# legacy_mk1_with_acc_16meg_crystal_and_TP.net
KiCad netlist of a schematic drawn in EAGLE
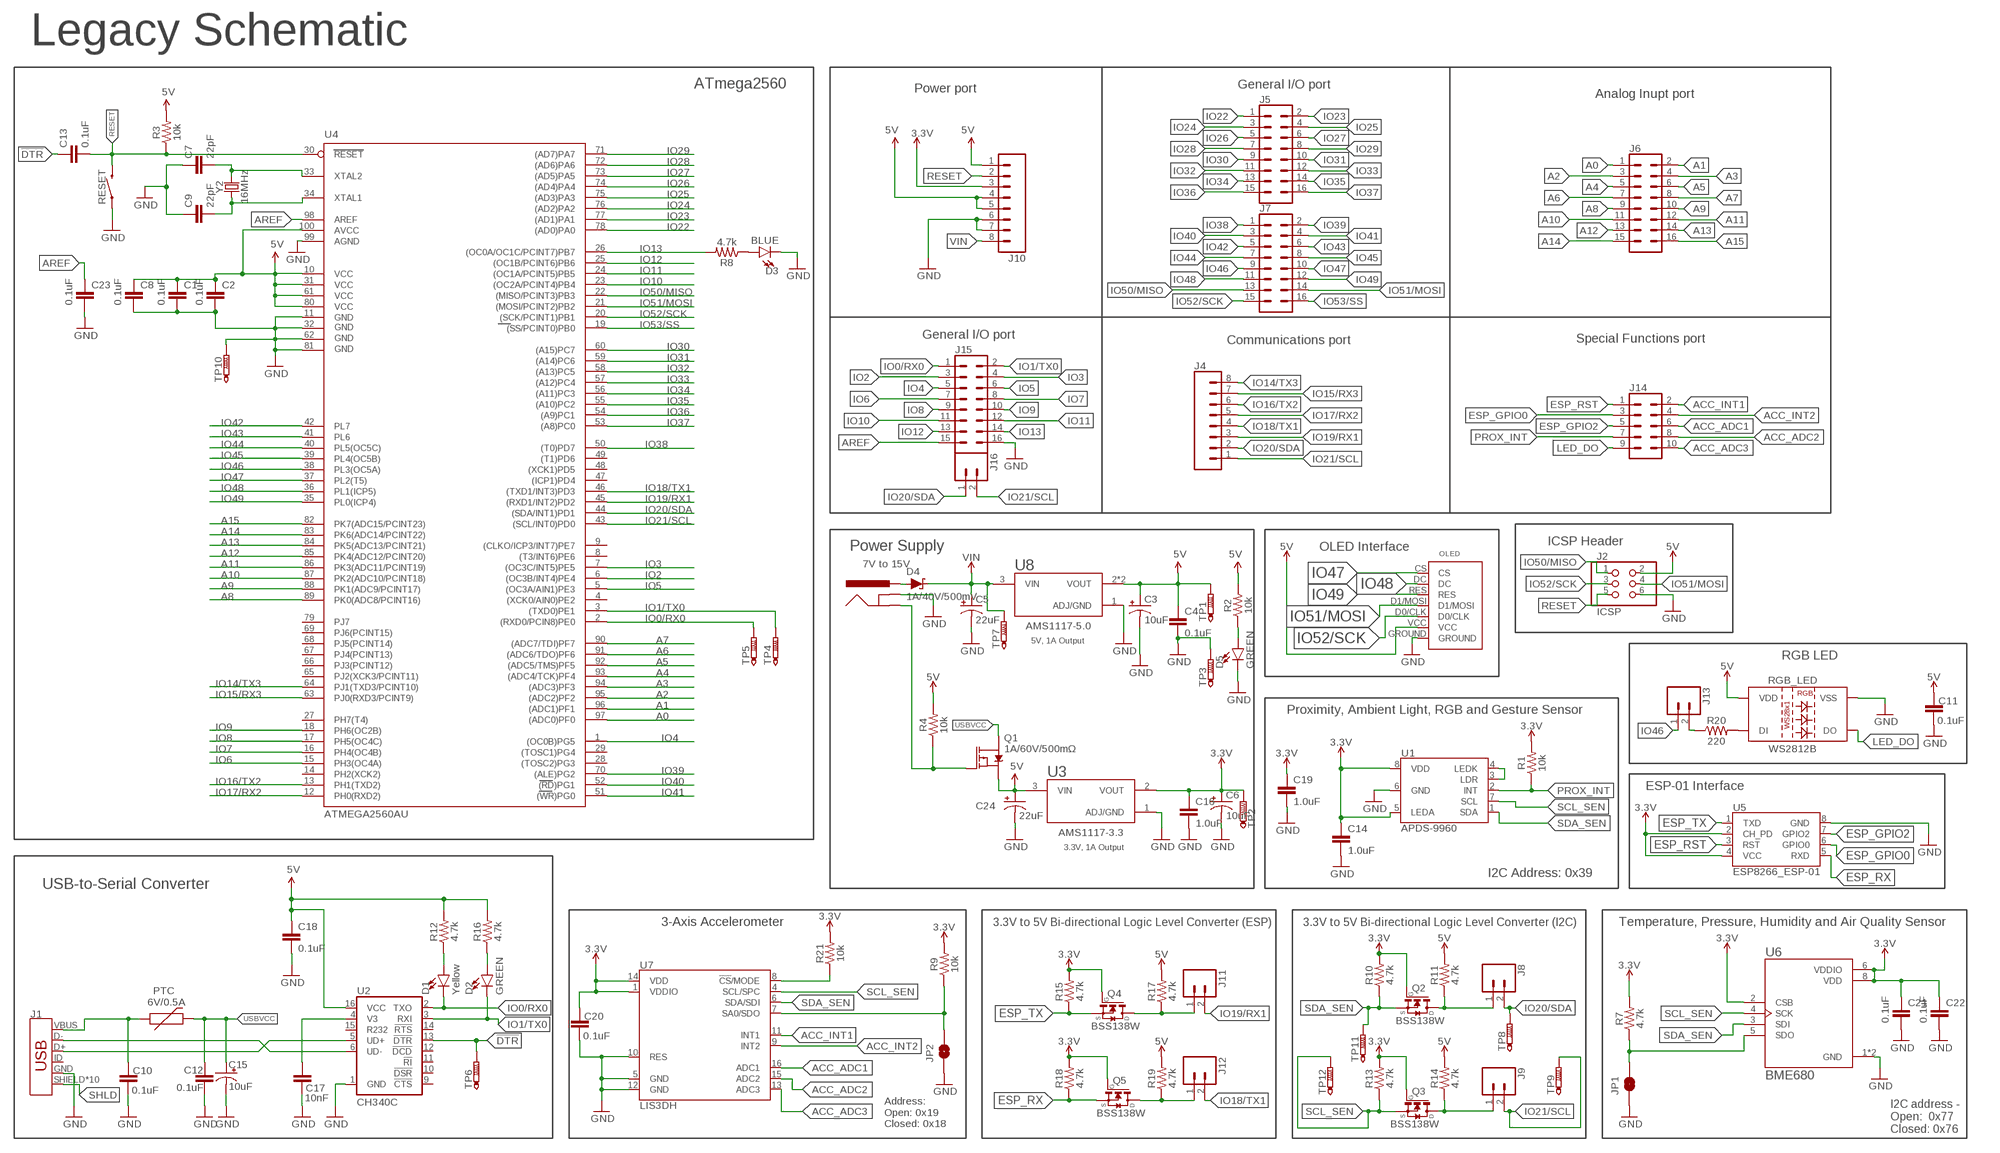
[diagram p0: schematic, sheet 1, part 1 of 2]

(export (version "E")
  (design (tool "Eeschema 10.0.6"))
  (components
    (comp (ref "C1")
      (value "0.1uF")
      (footprint "eagle-import:0603")
      (libsource (lib "eagle-import") (part "0.1UF-0603-25V-(+80/-20%)"))
    )
    (comp (ref "C2")
      (value "0.1uF")
      (footprint "eagle-import:0603")
      (libsource (lib "eagle-import") (part "0.1UF-0603-25V-(+80/-20%)"))
    )
    (comp (ref "C3")
      (value "10uF")
      (footprint "eagle-import:EIA3216")
      (libsource (lib "eagle-import") (part "10UF-POLAR-EIA3216-16V-10%(TANT)"))
    )
    (comp (ref "C4")
      (value "0.1uF")
      (footprint "eagle-import:0603")
      (libsource (lib "eagle-import") (part "0.1UF-0603-25V-(+80/-20%)"))
    )
    (comp (ref "C5")
      (value "22uF")
      (footprint "eagle-import:CT3528")
      (libsource (lib "eagle-import") (part "CPOL-USCT3528"))
    )
    (comp (ref "C6")
      (value "10uF")
      (footprint "eagle-import:EIA3216")
      (libsource (lib "eagle-import") (part "10UF-POLAR-EIA3216-16V-10%(TANT)"))
    )
    (comp (ref "C7")
      (value "22pF")
      (footprint "eagle-import:0603")
      (libsource (lib "eagle-import") (part "22PF-0603-50V-5%"))
    )
    (comp (ref "C8")
      (value "0.1uF")
      (footprint "eagle-import:0603")
      (libsource (lib "eagle-import") (part "0.1UF-0603-25V-(+80/-20%)"))
    )
    (comp (ref "C9")
      (value "22pF")
      (footprint "eagle-import:0603")
      (libsource (lib "eagle-import") (part "22PF-0603-50V-5%"))
    )
    (comp (ref "C10")
      (value "0.1uF")
      (footprint "eagle-import:0603")
      (libsource (lib "eagle-import") (part "0.1UF-0603-25V-(+80/-20%)"))
    )
    (comp (ref "C11")
      (value "0.1uF")
      (footprint "eagle-import:0603")
      (libsource (lib "eagle-import") (part "0.1UF-0603-25V-(+80/-20%)"))
    )
    (comp (ref "C12")
      (value "0.1uF")
      (footprint "eagle-import:0603")
      (libsource (lib "eagle-import") (part "0.1UF-0603-25V-(+80/-20%)"))
    )
    (comp (ref "C13")
      (value "0.1uF")
      (footprint "eagle-import:0603")
      (libsource (lib "eagle-import") (part "0.1UF-0603-25V-(+80/-20%)"))
    )
    (comp (ref "C14")
      (value "1.0uF")
      (footprint "eagle-import:0603-CAP")
      (libsource (lib "eagle-import") (part "1.0UF-16V-10%(0603)"))
    )
    (comp (ref "C15")
      (value "10uF")
      (footprint "eagle-import:EIA3216")
      (libsource (lib "eagle-import") (part "10UF-POLAR-EIA3216-16V-10%(TANT)"))
    )
    (comp (ref "C16")
      (value "1.0uF")
      (footprint "eagle-import:0603-CAP")
      (libsource (lib "eagle-import") (part "1.0UF-16V-10%(0603)"))
    )
    (comp (ref "C17")
      (value "10nF")
      (footprint "eagle-import:0603-CAP")
      (libsource (lib "eagle-import") (part "10NF/10000PF-50V-10%(0603)"))
    )
    (comp (ref "C18")
      (value "0.1uF")
      (footprint "eagle-import:0603")
      (libsource (lib "eagle-import") (part "0.1UF-0603-25V-(+80/-20%)"))
    )
    (comp (ref "C19")
      (value "1.0uF")
      (footprint "eagle-import:0603-CAP")
      (libsource (lib "eagle-import") (part "1.0UF-16V-10%(0603)"))
    )
    (comp (ref "C20")
      (value "0.1uF")
      (footprint "eagle-import:0603")
      (libsource (lib "eagle-import") (part "0.1UF-0603-25V-(+80/-20%)"))
    )
    (comp (ref "C21")
      (value "0.1uF")
      (footprint "eagle-import:0603")
      (libsource (lib "eagle-import") (part "0.1UF-0603-25V-(+80/-20%)"))
    )
    (comp (ref "C22")
      (value "0.1uF")
      (footprint "eagle-import:0603")
      (libsource (lib "eagle-import") (part "0.1UF-0603-25V-(+80/-20%)"))
    )
    (comp (ref "C23")
      (value "0.1uF")
      (footprint "eagle-import:0603")
      (libsource (lib "eagle-import") (part "0.1UF-0603-25V-(+80/-20%)"))
    )
    (comp (ref "C24")
      (value "22uF")
      (footprint "eagle-import:CT3528")
      (libsource (lib "eagle-import") (part "CPOL-USCT3528"))
    )
    (comp (ref "D1")
      (value "Yellow")
      (footprint "eagle-import:LED-0603")
      (libsource (lib "eagle-import") (part "LED-YELLOW0603"))
    )
    (comp (ref "D2")
      (value "GREEN")
      (footprint "eagle-import:LED-0603")
      (libsource (lib "eagle-import") (part "LED-GREEN0603"))
    )
    (comp (ref "D3")
      (value "BLUE")
      (footprint "eagle-import:LED-0603")
      (libsource (lib "eagle-import") (part "LED-BLUE0603"))
    )
    (comp (ref "D4")
      (value "1A/40V/500mV")
      (footprint "eagle-import:SMA-DIODE")
      (libsource (lib "eagle-import") (part "DIODE-SCHOTTKY-SS14"))
    )
    (comp (ref "D5")
      (value "GREEN")
      (footprint "eagle-import:LED-0603")
      (libsource (lib "eagle-import") (part "LED-GREEN0603"))
    )
    (comp (ref "J1")
      (value "AMP FCI 10103594-0001LF")
      (footprint "eagle-import:USB-MICROB-PTH-MILL")
      (libsource (lib "eagle-import") (part "USB_MICRO-B_HALF_PTH_MILL"))
    )
    (comp (ref "J2")
      (value "ICSP")
      (footprint "eagle-import:2X03")
      (libsource (lib "eagle-import") (part "PINHD-2X3"))
    )
    (comp (ref "J3")
      (value "POWER_JACKSLT")
      (footprint "eagle-import:POWER_JACK_SLOT")
      (libsource (lib "eagle-import") (part "POWER_JACKSLT"))
    )
    (comp (ref "J4")
      (value "CONN_08\"")
      (footprint "eagle-import:1X08")
      (libsource (lib "eagle-import") (part "CONN_08{dblquote}"))
    )
    (comp (ref "J5")
      (value "CONN_08X2_HEADER")
      (footprint "eagle-import:2X8")
      (libsource (lib "eagle-import") (part "CONN_08X2_HEADER"))
    )
    (comp (ref "J6")
      (value "CONN_08X2_HEADER")
      (footprint "eagle-import:2X8")
      (libsource (lib "eagle-import") (part "CONN_08X2_HEADER"))
    )
    (comp (ref "J7")
      (value "CONN_08X2_HEADER")
      (footprint "eagle-import:2X8")
      (libsource (lib "eagle-import") (part "CONN_08X2_HEADER"))
    )
    (comp (ref "J8")
      (value "CONN_02")
      (footprint "eagle-import:1X02")
      (libsource (lib "eagle-import") (part "CONN_02"))
    )
    (comp (ref "J9")
      (value "CONN_02")
      (footprint "eagle-import:1X02")
      (libsource (lib "eagle-import") (part "CONN_02"))
    )
    (comp (ref "J10")
      (value "CONN_08\"")
      (footprint "eagle-import:1X08")
      (libsource (lib "eagle-import") (part "CONN_08{dblquote}"))
    )
    (comp (ref "J11")
      (value "CONN_02")
      (footprint "eagle-import:1X02")
      (libsource (lib "eagle-import") (part "CONN_02"))
    )
    (comp (ref "J12")
      (value "CONN_02")
      (footprint "eagle-import:1X02")
      (libsource (lib "eagle-import") (part "CONN_02"))
    )
    (comp (ref "J13")
      (value "CONN_02")
      (footprint "eagle-import:1X02")
      (libsource (lib "eagle-import") (part "CONN_02"))
    )
    (comp (ref "J14")
      (value "CONN_05X2PTH")
      (footprint "eagle-import:2X5")
      (libsource (lib "eagle-import") (part "CONN_05X2PTH"))
    )
    (comp (ref "J15")
      (value "CONN_08X2_HEADER")
      (footprint "eagle-import:2X8")
      (libsource (lib "eagle-import") (part "CONN_08X2_HEADER"))
    )
    (comp (ref "J16")
      (value "CONN_02")
      (footprint "eagle-import:1X02")
      (libsource (lib "eagle-import") (part "CONN_02"))
    )
    (comp (ref "JP1")
      (value "JUMPER-SMT_2_NO_SILK")
      (footprint "eagle-import:SMT-JUMPER_2_NO_SILK")
      (libsource (lib "eagle-import") (part "JUMPER-SMT_2_NO_SILK"))
    )
    (comp (ref "JP2")
      (value "JUMPER-SMT_2_NO_SILK")
      (footprint "eagle-import:SMT-JUMPER_2_NO_SILK")
      (libsource (lib "eagle-import") (part "JUMPER-SMT_2_NO_SILK"))
    )
    (comp (ref "OLED")
      (value "OLED_SHIELD")
      (footprint "eagle-import:OLED_SHIELD")
      (libsource (lib "eagle-import") (part "OLED_SHIELD"))
    )
    (comp (ref "PTC")
      (value "6V/0.5A")
      (footprint "eagle-import:1206")
      (libsource (lib "eagle-import") (part "PPTC_6V500MA-2"))
    )
    (comp (ref "Q1")
      (value "1A/60V/500mΩ")
      (footprint "eagle-import:SOT23-3")
      (libsource (lib "eagle-import") (part "MOSFET-PCH-ZXMP6A13F"))
    )
    (comp (ref "Q2")
      (value "BSS138W")
      (footprint "eagle-import:SOT323-R")
      (fields (field (name "DIGI-KEY_PART_NUMBER") "BSS138WCT-ND") (field (name "MF") "ON Semiconductor"))
      (libsource (lib "eagle-import") (part "BSS138W"))
    )
    (comp (ref "Q3")
      (value "BSS138W")
      (footprint "eagle-import:SOT323-R")
      (fields (field (name "DIGI-KEY_PART_NUMBER") "BSS138WCT-ND") (field (name "MF") "ON Semiconductor"))
      (libsource (lib "eagle-import") (part "BSS138W"))
    )
    (comp (ref "Q4")
      (value "BSS138W")
      (footprint "eagle-import:SOT323-R")
      (fields (field (name "DIGI-KEY_PART_NUMBER") "BSS138WCT-ND") (field (name "MF") "ON Semiconductor"))
      (libsource (lib "eagle-import") (part "BSS138W"))
    )
    (comp (ref "Q5")
      (value "BSS138W")
      (footprint "eagle-import:SOT323-R")
      (fields (field (name "DIGI-KEY_PART_NUMBER") "BSS138WCT-ND") (field (name "MF") "ON Semiconductor"))
      (libsource (lib "eagle-import") (part "BSS138W"))
    )
    (comp (ref "R1")
      (value "10k")
      (footprint "eagle-import:0603")
      (libsource (lib "eagle-import") (part "10KOHM-0603-1/10W-1%"))
    )
    (comp (ref "R2")
      (value "10k")
      (footprint "eagle-import:0603")
      (libsource (lib "eagle-import") (part "10KOHM-0603-1/10W-1%"))
    )
    (comp (ref "R3")
      (value "10k")
      (footprint "eagle-import:0603")
      (libsource (lib "eagle-import") (part "10KOHM-0603-1/10W-1%"))
    )
    (comp (ref "R4")
      (value "10k")
      (footprint "eagle-import:0603")
      (libsource (lib "eagle-import") (part "10KOHM-0603-1/10W-1%"))
    )
    (comp (ref "R7")
      (value "4.7k")
      (footprint "eagle-import:0603")
      (libsource (lib "eagle-import") (part "4.7KOHM-0603-1/10W-1%"))
    )
    (comp (ref "R8")
      (value "4.7k")
      (footprint "eagle-import:0603")
      (libsource (lib "eagle-import") (part "4.7KOHM-0603-1/10W-1%"))
    )
    (comp (ref "R9")
      (value "10k")
      (footprint "eagle-import:0603")
      (libsource (lib "eagle-import") (part "10KOHM-0603-1/10W-1%"))
    )
    (comp (ref "R10")
      (value "4.7k")
      (footprint "eagle-import:0603")
      (libsource (lib "eagle-import") (part "4.7KOHM-0603-1/10W-1%"))
    )
    (comp (ref "R11")
      (value "4.7k")
      (footprint "eagle-import:0603")
      (libsource (lib "eagle-import") (part "4.7KOHM-0603-1/10W-1%"))
    )
    (comp (ref "R12")
      (value "4.7k")
      (footprint "eagle-import:0603")
      (libsource (lib "eagle-import") (part "4.7KOHM-0603-1/10W-1%"))
    )
    (comp (ref "R13")
      (value "4.7k")
      (footprint "eagle-import:0603")
      (libsource (lib "eagle-import") (part "4.7KOHM-0603-1/10W-1%"))
    )
    (comp (ref "R14")
      (value "4.7k")
      (footprint "eagle-import:0603")
      (libsource (lib "eagle-import") (part "4.7KOHM-0603-1/10W-1%"))
    )
    (comp (ref "R15")
      (value "4.7k")
      (footprint "eagle-import:0603")
      (libsource (lib "eagle-import") (part "4.7KOHM-0603-1/10W-1%"))
    )
    (comp (ref "R16")
      (value "4.7k")
      (footprint "eagle-import:0603")
      (libsource (lib "eagle-import") (part "4.7KOHM-0603-1/10W-1%"))
    )
    (comp (ref "R17")
      (value "4.7k")
      (footprint "eagle-import:0603")
      (libsource (lib "eagle-import") (part "4.7KOHM-0603-1/10W-1%"))
    )
    (comp (ref "R18")
      (value "4.7k")
      (footprint "eagle-import:0603")
      (libsource (lib "eagle-import") (part "4.7KOHM-0603-1/10W-1%"))
    )
    (comp (ref "R19")
      (value "4.7k")
      (footprint "eagle-import:0603")
      (libsource (lib "eagle-import") (part "4.7KOHM-0603-1/10W-1%"))
    )
    (comp (ref "R20")
      (value "220")
      (footprint "eagle-import:0603")
      (libsource (lib "eagle-import") (part "220OHM-0603-1/10W-1%"))
    )
    (comp (ref "R21")
      (value "10k")
      (footprint "eagle-import:0603")
      (libsource (lib "eagle-import") (part "10KOHM-0603-1/10W-1%"))
    )
    (comp (ref "RESET")
      (value "MOMENTARY-SWITCH-SPST-PTH-6.0MM")
      (footprint "eagle-import:TACTILE_SWITCH_PTH_6.0MM")
      (libsource (lib "eagle-import") (part "MOMENTARY-SWITCH-SPST-PTH-6.0MM"))
    )
    (comp (ref "RGB_LED")
      (value "WS2812B")
      (footprint "eagle-import:WS2812B")
      (libsource (lib "eagle-import") (part "WS2812B"))
    )
    (comp (ref "TP1")
      (value "PTR1B1,27")
      (footprint "eagle-import:B1,27")
      (libsource (lib "eagle-import") (part "PTR1B1,27"))
    )
    (comp (ref "TP2")
      (value "PTR1B1,27")
      (footprint "eagle-import:B1,27")
      (libsource (lib "eagle-import") (part "PTR1B1,27"))
    )
    (comp (ref "TP3")
      (value "PTR1B1,27")
      (footprint "eagle-import:B1,27")
      (libsource (lib "eagle-import") (part "PTR1B1,27"))
    )
    (comp (ref "TP4")
      (value "PTR1B1,27")
      (footprint "eagle-import:B1,27")
      (libsource (lib "eagle-import") (part "PTR1B1,27"))
    )
    (comp (ref "TP5")
      (value "PTR1B1,27")
      (footprint "eagle-import:B1,27")
      (libsource (lib "eagle-import") (part "PTR1B1,27"))
    )
    (comp (ref "TP6")
      (value "PTR1B1,27")
      (footprint "eagle-import:B1,27")
      (libsource (lib "eagle-import") (part "PTR1B1,27"))
    )
    (comp (ref "TP7")
      (value "PTR1B1,27")
      (footprint "eagle-import:B1,27")
      (libsource (lib "eagle-import") (part "PTR1B1,27"))
    )
    (comp (ref "TP8")
      (value "PTR1B1,27")
      (footprint "eagle-import:B1,27")
      (libsource (lib "eagle-import") (part "PTR1B1,27"))
    )
    (comp (ref "TP9")
      (value "PTR1B1,27")
      (footprint "eagle-import:B1,27")
      (libsource (lib "eagle-import") (part "PTR1B1,27"))
    )
    (comp (ref "TP10")
      (value "PTR1B1,27")
      (footprint "eagle-import:B1,27")
      (libsource (lib "eagle-import") (part "PTR1B1,27"))
    )
    (comp (ref "TP11")
      (value "PTR1B1,27")
      (footprint "eagle-import:B1,27")
      (libsource (lib "eagle-import") (part "PTR1B1,27"))
    )
    (comp (ref "TP12")
      (value "PTR1B1,27")
      (footprint "eagle-import:B1,27")
      (libsource (lib "eagle-import") (part "PTR1B1,27"))
    )
    (comp (ref "U1")
      (value "APDS-9960")
      (footprint "eagle-import:APDS-9960")
      (fields (field (name "MF") "Broadcom Limited"))
      (libsource (lib "eagle-import") (part "APDS-9960"))
    )
    (comp (ref "U2")
      (value "CH340C")
      (footprint "eagle-import:SO016")
      (libsource (lib "eagle-import") (part "CH340C"))
    )
    (comp (ref "U3")
      (value "AMS1117-3.3")
      (footprint "eagle-import:SOT229P700X180-4N")
      (fields (field (name "MF") "Advanced Monolithic Systems"))
      (libsource (lib "eagle-import") (part "AMS1117-3.3"))
    )
    (comp (ref "U4")
      (value "ATMEGA2560AU")
      (footprint "eagle-import:TQFP100")
      (libsource (lib "eagle-import") (part "ATMEGA2560AU"))
    )
    (comp (ref "U5")
      (value "ESP8266_ESP-01")
      (footprint "eagle-import:ESP8266_ESP-01")
      (libsource (lib "eagle-import") (part "ESP8266_ESP-01"))
    )
    (comp (ref "U6")
      (value "BME680")
      (footprint "eagle-import:PSON80P300X300X100-8N")
      (fields (field (name "DIGI-KEY_PART_NUMBER") "828-1077-1-ND") (field (name "MF") "Bosch Sensortec"))
      (libsource (lib "eagle-import") (part "BME680"))
    )
    (comp (ref "U7")
      (value "LIS3DH")
      (footprint "eagle-import:LGA-16-3X3")
      (libsource (lib "eagle-import") (part "LIS3DH"))
    )
    (comp (ref "U8")
      (value "AMS1117-5.0")
      (footprint "eagle-import:SOT229P700X180-4N")
      (fields (field (name "MF") "Advanced Monolithic Systems"))
      (libsource (lib "eagle-import") (part "AMS1117-5.0"))
    )
    (comp (ref "Y2")
      (value "16MHz")
      (footprint "eagle-import:HC49US")
      (libsource (lib "eagle-import") (part "CRYSTAL-16MHZPTH-HC49US"))
    )
  )
  (nets
    (net (code "1") (name "/~{DTR}") (class "Default")
      (node (ref "C13") (pin "1") (pinfunction "1_1") (pintype "passive"))
      (node (ref "TP6") (pin "TP") (pinfunction "TP_TP") (pintype "input"))
      (node (ref "U2") (pin "13") (pinfunction "~{DTR}_13") (pintype "bidirectional"))
    )
    (net (code "2") (name "3.3V") (class "Default")
      (node (ref "C14") (pin "1") (pinfunction "1_1") (pintype "passive"))
      (node (ref "C16") (pin "1") (pinfunction "1_1") (pintype "passive"))
      (node (ref "C19") (pin "1") (pinfunction "1_1") (pintype "passive"))
      (node (ref "C20") (pin "1") (pinfunction "1_1") (pintype "passive"))
      (node (ref "C21") (pin "1") (pinfunction "1_1") (pintype "passive"))
      (node (ref "C22") (pin "1") (pinfunction "1_1") (pintype "passive"))
      (node (ref "C6") (pin "+") (pinfunction "+_+") (pintype "passive"))
      (node (ref "J10") (pin "3") (pinfunction "3_3") (pintype "passive"))
      (node (ref "Q2") (pin "1") (pinfunction "G_1") (pintype "passive"))
      (node (ref "Q3") (pin "1") (pinfunction "G_1") (pintype "passive"))
      (node (ref "Q4") (pin "1") (pinfunction "G_1") (pintype "passive"))
      (node (ref "Q5") (pin "1") (pinfunction "G_1") (pintype "passive"))
      (node (ref "R1") (pin "2") (pinfunction "2_2") (pintype "passive"))
      (node (ref "R10") (pin "2") (pinfunction "2_2") (pintype "passive"))
      (node (ref "R13") (pin "2") (pinfunction "2_2") (pintype "passive"))
      (node (ref "R15") (pin "2") (pinfunction "2_2") (pintype "passive"))
      (node (ref "R18") (pin "2") (pinfunction "2_2") (pintype "passive"))
      (node (ref "R21") (pin "2") (pinfunction "2_2") (pintype "passive"))
      (node (ref "R7") (pin "2") (pinfunction "2_2") (pintype "passive"))
      (node (ref "R9") (pin "2") (pinfunction "2_2") (pintype "passive"))
      (node (ref "TP2") (pin "TP") (pinfunction "TP_TP") (pintype "input"))
      (node (ref "U1") (pin "5") (pinfunction "LEDA_5") (pintype "bidirectional"))
      (node (ref "U1") (pin "8") (pinfunction "VDD_8") (pintype "bidirectional"))
      (node (ref "U3") (pin "2") (pinfunction "VOUT_2") (pintype "output"))
      (node (ref "U5") (pin "2") (pinfunction "CH_PD_2") (pintype "bidirectional"))
      (node (ref "U5") (pin "4") (pinfunction "VCC_4") (pintype "bidirectional"))
      (node (ref "U6") (pin "2") (pinfunction "CSB_2") (pintype "input"))
      (node (ref "U6") (pin "6") (pinfunction "VDDIO_6") (pintype "power_in"))
      (node (ref "U6") (pin "8") (pinfunction "VDD_8") (pintype "power_in"))
      (node (ref "U7") (pin "1") (pinfunction "VDDIO_1") (pintype "bidirectional"))
      (node (ref "U7") (pin "14") (pinfunction "VDD_14") (pintype "bidirectional"))
    )
    (net (code "3") (name "5V") (class "Default")
      (node (ref "C1") (pin "1") (pinfunction "1_1") (pintype "passive"))
      (node (ref "C11") (pin "1") (pinfunction "1_1") (pintype "passive"))
      (node (ref "C18") (pin "1") (pinfunction "1_1") (pintype "passive"))
      (node (ref "C2") (pin "1") (pinfunction "1_1") (pintype "passive"))
      (node (ref "C24") (pin "+") (pinfunction "+_+") (pintype "passive"))
      (node (ref "C3") (pin "+") (pinfunction "+_+") (pintype "passive"))
      (node (ref "C4") (pin "1") (pinfunction "1_1") (pintype "passive"))
      (node (ref "C8") (pin "1") (pinfunction "1_1") (pintype "passive"))
      (node (ref "J10") (pin "1") (pinfunction "1_1") (pintype "passive"))
      (node (ref "J10") (pin "4") (pinfunction "4_4") (pintype "passive"))
      (node (ref "J10") (pin "5") (pinfunction "5_5") (pintype "passive"))
      (node (ref "J2") (pin "2") (pinfunction "2_2") (pintype "passive"))
      (node (ref "OLED") (pin "VCC") (pinfunction "VCC_VCC") (pintype "bidirectional"))
      (node (ref "Q1") (pin "2") (pinfunction "S_2") (pintype "bidirectional"))
      (node (ref "R11") (pin "2") (pinfunction "2_2") (pintype "passive"))
      (node (ref "R12") (pin "2") (pinfunction "2_2") (pintype "passive"))
      (node (ref "R14") (pin "2") (pinfunction "2_2") (pintype "passive"))
      (node (ref "R16") (pin "2") (pinfunction "2_2") (pintype "passive"))
      (node (ref "R17") (pin "2") (pinfunction "2_2") (pintype "passive"))
      (node (ref "R19") (pin "2") (pinfunction "2_2") (pintype "passive"))
      (node (ref "R2") (pin "2") (pinfunction "2_2") (pintype "passive"))
      (node (ref "R3") (pin "2") (pinfunction "2_2") (pintype "passive"))
      (node (ref "R4") (pin "2") (pinfunction "2_2") (pintype "passive"))
      (node (ref "RGB_LED") (pin "1") (pinfunction "VDD_1") (pintype "bidirectional"))
      (node (ref "TP1") (pin "TP") (pinfunction "TP_TP") (pintype "input"))
      (node (ref "U2") (pin "16") (pinfunction "VCC_16") (pintype "bidirectional"))
      (node (ref "U3") (pin "3") (pinfunction "VIN_3") (pintype "input"))
      (node (ref "U4") (pin "10") (pinfunction "VCC_10") (pintype "power_in"))
      (node (ref "U4") (pin "100") (pinfunction "AVCC_100") (pintype "power_in"))
      (node (ref "U4") (pin "31") (pinfunction "VCC1_31") (pintype "power_in"))
      (node (ref "U4") (pin "61") (pinfunction "VCC2_61") (pintype "power_in"))
      (node (ref "U4") (pin "80") (pinfunction "VCC3_80") (pintype "power_in"))
      (node (ref "U8") (pin "2") (pinfunction "VOUT_2") (pintype "output"))
      (node (ref "U8") (pin "4") (pinfunction "VOUT_4") (pintype "output"))
    )
    (net (code "4") (name "A0") (class "Default")
      (node (ref "J6") (pin "1") (pinfunction "1_1") (pintype "passive"))
      (node (ref "U4") (pin "97") (pinfunction "(ADC0)PF0_97") (pintype "bidirectional"))
    )
    (net (code "5") (name "A1") (class "Default")
      (node (ref "J6") (pin "2") (pinfunction "2_2") (pintype "passive"))
      (node (ref "U4") (pin "96") (pinfunction "(ADC1)PF1_96") (pintype "bidirectional"))
    )
    (net (code "6") (name "A2") (class "Default")
      (node (ref "J6") (pin "3") (pinfunction "3_3") (pintype "passive"))
      (node (ref "U4") (pin "95") (pinfunction "(ADC2)PF2_95") (pintype "bidirectional"))
    )
    (net (code "7") (name "A3") (class "Default")
      (node (ref "J6") (pin "4") (pinfunction "4_4") (pintype "passive"))
      (node (ref "U4") (pin "94") (pinfunction "(ADC3)PF3_94") (pintype "bidirectional"))
    )
    (net (code "8") (name "A4") (class "Default")
      (node (ref "J6") (pin "5") (pinfunction "5_5") (pintype "passive"))
      (node (ref "U4") (pin "93") (pinfunction "(ADC4/TCK)PF4_93") (pintype "bidirectional"))
    )
    (net (code "9") (name "A5") (class "Default")
      (node (ref "J6") (pin "6") (pinfunction "6_6") (pintype "passive"))
      (node (ref "U4") (pin "92") (pinfunction "(ADC5/TMS)PF5_92") (pintype "bidirectional"))
    )
    (net (code "10") (name "A6") (class "Default")
      (node (ref "J6") (pin "7") (pinfunction "7_7") (pintype "passive"))
      (node (ref "U4") (pin "91") (pinfunction "(ADC6/TDO)PF6_91") (pintype "bidirectional"))
    )
    (net (code "11") (name "A7") (class "Default")
      (node (ref "J6") (pin "8") (pinfunction "8_8") (pintype "passive"))
      (node (ref "U4") (pin "90") (pinfunction "(ADC7/TDI)PF7_90") (pintype "bidirectional"))
    )
    (net (code "12") (name "A8") (class "Default")
      (node (ref "J6") (pin "9") (pinfunction "9_9") (pintype "passive"))
      (node (ref "U4") (pin "89") (pinfunction "PK0(ADC8/PCINT16)_89") (pintype "bidirectional"))
    )
    (net (code "13") (name "A9") (class "Default")
      (node (ref "J6") (pin "10") (pinfunction "10_10") (pintype "passive"))
      (node (ref "U4") (pin "88") (pinfunction "PK1(ADC9/PCINT17)_88") (pintype "bidirectional"))
    )
    (net (code "14") (name "A10") (class "Default")
      (node (ref "J6") (pin "11") (pinfunction "11_11") (pintype "passive"))
      (node (ref "U4") (pin "87") (pinfunction "PK2(ADC10/PCINT18)_87") (pintype "bidirectional"))
    )
    (net (code "15") (name "A11") (class "Default")
      (node (ref "J6") (pin "12") (pinfunction "12_12") (pintype "passive"))
      (node (ref "U4") (pin "86") (pinfunction "PK3(ADC11/PCINT19)_86") (pintype "bidirectional"))
    )
    (net (code "16") (name "A12") (class "Default")
      (node (ref "J6") (pin "13") (pinfunction "13_13") (pintype "passive"))
      (node (ref "U4") (pin "85") (pinfunction "PK4(ADC12/PCINT20)_85") (pintype "bidirectional"))
    )
    (net (code "17") (name "A13") (class "Default")
      (node (ref "J6") (pin "14") (pinfunction "14_14") (pintype "passive"))
      (node (ref "U4") (pin "84") (pinfunction "PK5(ADC13/PCINT21)_84") (pintype "bidirectional"))
    )
    (net (code "18") (name "A14") (class "Default")
      (node (ref "J6") (pin "15") (pinfunction "15_15") (pintype "passive"))
      (node (ref "U4") (pin "83") (pinfunction "PK6(ADC14/PCINT22)_83") (pintype "bidirectional"))
    )
    (net (code "19") (name "A15") (class "Default")
      (node (ref "J6") (pin "16") (pinfunction "16_16") (pintype "passive"))
      (node (ref "U4") (pin "82") (pinfunction "PK7(ADC15/PCINT23)_82") (pintype "bidirectional"))
    )
    (net (code "20") (name "ACC_ADC1") (class "Default")
      (node (ref "J14") (pin "6") (pinfunction "6_6") (pintype "passive"))
      (node (ref "U7") (pin "16") (pinfunction "ADC1_16") (pintype "bidirectional"))
    )
    (net (code "21") (name "ACC_ADC2") (class "Default")
      (node (ref "J14") (pin "8") (pinfunction "8_8") (pintype "passive"))
      (node (ref "U7") (pin "15") (pinfunction "ADC2_15") (pintype "bidirectional"))
    )
    (net (code "22") (name "ACC_ADC3") (class "Default")
      (node (ref "J14") (pin "10") (pinfunction "10_10") (pintype "passive"))
      (node (ref "U7") (pin "13") (pinfunction "ADC3_13") (pintype "bidirectional"))
    )
    (net (code "23") (name "ACC_INT1") (class "Default")
      (node (ref "J14") (pin "2") (pinfunction "2_2") (pintype "passive"))
      (node (ref "U7") (pin "11") (pinfunction "INT1_11") (pintype "bidirectional"))
    )
    (net (code "24") (name "ACC_INT2") (class "Default")
      (node (ref "J14") (pin "4") (pinfunction "4_4") (pintype "passive"))
      (node (ref "U7") (pin "9") (pinfunction "INT2_9") (pintype "bidirectional"))
    )
    (net (code "25") (name "AREF") (class "Default")
      (node (ref "C23") (pin "1") (pinfunction "1_1") (pintype "passive"))
      (node (ref "J15") (pin "15") (pinfunction "15_15") (pintype "passive"))
      (node (ref "U4") (pin "98") (pinfunction "AREF_98") (pintype "bidirectional"))
    )
    (net (code "26") (name "ESP_GPIO0") (class "Default")
      (node (ref "J14") (pin "3") (pinfunction "3_3") (pintype "passive"))
      (node (ref "U5") (pin "6") (pinfunction "GPIO0_6") (pintype "bidirectional"))
    )
    (net (code "27") (name "ESP_GPIO2") (class "Default")
      (node (ref "J14") (pin "5") (pinfunction "5_5") (pintype "passive"))
      (node (ref "U5") (pin "7") (pinfunction "GPIO2_7") (pintype "bidirectional"))
    )
    (net (code "28") (name "ESP_RST") (class "Default")
      (node (ref "J14") (pin "1") (pinfunction "1_1") (pintype "passive"))
      (node (ref "U5") (pin "3") (pinfunction "RST_3") (pintype "bidirectional"))
    )
    (net (code "29") (name "ESP_RX") (class "Default")
      (node (ref "Q5") (pin "2") (pinfunction "S_2") (pintype "passive"))
      (node (ref "R18") (pin "1") (pinfunction "1_1") (pintype "passive"))
      (node (ref "U5") (pin "5") (pinfunction "RXD_5") (pintype "bidirectional"))
    )
    (net (code "30") (name "ESP_TX") (class "Default")
      (node (ref "Q4") (pin "2") (pinfunction "S_2") (pintype "passive"))
      (node (ref "R15") (pin "1") (pinfunction "1_1") (pintype "passive"))
      (node (ref "U5") (pin "1") (pinfunction "TXD_1") (pintype "bidirectional"))
    )
    (net (code "31") (name "GND") (class "Default")
      (node (ref "C1") (pin "2") (pinfunction "2_2") (pintype "passive"))
      (node (ref "C10") (pin "2") (pinfunction "2_2") (pintype "passive"))
      (node (ref "C11") (pin "2") (pinfunction "2_2") (pintype "passive"))
      (node (ref "C12") (pin "2") (pinfunction "2_2") (pintype "passive"))
      (node (ref "C14") (pin "2") (pinfunction "2_2") (pintype "passive"))
      (node (ref "C15") (pin "-") (pinfunction "-_-") (pintype "passive"))
      (node (ref "C16") (pin "2") (pinfunction "2_2") (pintype "passive"))
      (node (ref "C17") (pin "2") (pinfunction "2_2") (pintype "passive"))
      (node (ref "C18") (pin "2") (pinfunction "2_2") (pintype "passive"))
      (node (ref "C19") (pin "2") (pinfunction "2_2") (pintype "passive"))
      (node (ref "C2") (pin "2") (pinfunction "2_2") (pintype "passive"))
      (node (ref "C20") (pin "2") (pinfunction "2_2") (pintype "passive"))
      (node (ref "C21") (pin "2") (pinfunction "2_2") (pintype "passive"))
      (node (ref "C22") (pin "2") (pinfunction "2_2") (pintype "passive"))
      (node (ref "C23") (pin "2") (pinfunction "2_2") (pintype "passive"))
      (node (ref "C24") (pin "-") (pinfunction "-_-") (pintype "passive"))
      (node (ref "C3") (pin "-") (pinfunction "-_-") (pintype "passive"))
      (node (ref "C4") (pin "2") (pinfunction "2_2") (pintype "passive"))
      (node (ref "C5") (pin "-") (pinfunction "-_-") (pintype "passive"))
      (node (ref "C6") (pin "-") (pinfunction "-_-") (pintype "passive"))
      (node (ref "C7") (pin "1") (pinfunction "1_1") (pintype "passive"))
      (node (ref "C8") (pin "2") (pinfunction "2_2") (pintype "passive"))
      (node (ref "C9") (pin "1") (pinfunction "1_1") (pintype "passive"))
      (node (ref "D3") (pin "C") (pinfunction "C_C") (pintype "passive"))
      (node (ref "D5") (pin "C") (pinfunction "C_C") (pintype "passive"))
      (node (ref "J1") (pin "GND") (pinfunction "GND_GND") (pintype "power_in"))
      (node (ref "J10") (pin "6") (pinfunction "6_6") (pintype "passive"))
      (node (ref "J10") (pin "7") (pinfunction "7_7") (pintype "passive"))
      (node (ref "J15") (pin "16") (pinfunction "16_16") (pintype "passive"))
      (node (ref "J2") (pin "6") (pinfunction "6_6") (pintype "passive"))
      (node (ref "J3") (pin "GND@1") (pinfunction "GNDBREAK_GND@1") (pintype "bidirectional"))
      (node (ref "JP1") (pin "1") (pinfunction "1_1") (pintype "passive"))
      (node (ref "JP2") (pin "1") (pinfunction "1_1") (pintype "passive"))
      (node (ref "OLED") (pin "GROUND") (pinfunction "GROUND_GROUND") (pintype "bidirectional"))
      (node (ref "RESET") (pin "1") (pinfunction "1_1") (pintype "passive"))
      (node (ref "RGB_LED") (pin "3") (pinfunction "VSS_3") (pintype "bidirectional"))
      (node (ref "TP10") (pin "TP") (pinfunction "TP_TP") (pintype "input"))
      (node (ref "TP3") (pin "TP") (pinfunction "TP_TP") (pintype "input"))
      (node (ref "U1") (pin "6") (pinfunction "GND_6") (pintype "bidirectional"))
      (node (ref "U2") (pin "1") (pinfunction "GND_1") (pintype "bidirectional"))
      (node (ref "U3") (pin "1") (pinfunction "ADJ/GND_1") (pintype "power_in"))
      (node (ref "U4") (pin "11") (pinfunction "GND_11") (pintype "power_in"))
      (node (ref "U4") (pin "32") (pinfunction "GND1_32") (pintype "power_in"))
      (node (ref "U4") (pin "62") (pinfunction "GND2_62") (pintype "power_in"))
      (node (ref "U4") (pin "81") (pinfunction "GND3_81") (pintype "power_in"))
      (node (ref "U4") (pin "99") (pinfunction "AGND_99") (pintype "power_in"))
      (node (ref "U5") (pin "8") (pinfunction "GND_8") (pintype "bidirectional"))
      (node (ref "U6") (pin "1") (pinfunction "GND_1") (pintype "power_in"))
      (node (ref "U6") (pin "7") (pinfunction "GND_7") (pintype "power_in"))
      (node (ref "U7") (pin "10") (pinfunction "RES_10") (pintype "bidirectional"))
      (node (ref "U7") (pin "12") (pinfunction "GND_12") (pintype "bidirectional"))
      (node (ref "U7") (pin "5") (pinfunction "GND_5") (pintype "bidirectional"))
      (node (ref "U8") (pin "1") (pinfunction "ADJ/GND_1") (pintype "power_in"))
    )
    (net (code "32") (name "IO0{slash}RX0") (class "Default")
      (node (ref "D1") (pin "C") (pinfunction "C_C") (pintype "passive"))
      (node (ref "J15") (pin "1") (pinfunction "1_1") (pintype "passive"))
      (node (ref "TP5") (pin "TP") (pinfunction "TP_TP") (pintype "input"))
      (node (ref "U2") (pin "2") (pinfunction "TXO_2") (pintype "bidirectional"))
      (node (ref "U4") (pin "2") (pinfunction "(RXD0/PCIN8)PE0_2") (pintype "bidirectional"))
    )
    (net (code "33") (name "IO1{slash}TX0") (class "Default")
      (node (ref "D2") (pin "C") (pinfunction "C_C") (pintype "passive"))
      (node (ref "J15") (pin "2") (pinfunction "2_2") (pintype "passive"))
      (node (ref "TP4") (pin "TP") (pinfunction "TP_TP") (pintype "input"))
      (node (ref "U2") (pin "3") (pinfunction "RXI_3") (pintype "bidirectional"))
      (node (ref "U4") (pin "3") (pinfunction "(TXD0)PE1_3") (pintype "bidirectional"))
    )
    (net (code "34") (name "IO2") (class "Default")
      (node (ref "J15") (pin "3") (pinfunction "3_3") (pintype "passive"))
      (node (ref "U4") (pin "6") (pinfunction "(OC3B/INT4)PE4_6") (pintype "bidirectional"))
    )
    (net (code "35") (name "IO3") (class "Default")
      (node (ref "J15") (pin "4") (pinfunction "4_4") (pintype "passive"))
      (node (ref "U4") (pin "7") (pinfunction "(OC3C/INT5)PE5_7") (pintype "bidirectional"))
    )
    (net (code "36") (name "IO4") (class "Default")
      (node (ref "J15") (pin "5") (pinfunction "5_5") (pintype "passive"))
      (node (ref "U4") (pin "1") (pinfunction "(OC0B)PG5_1") (pintype "bidirectional"))
    )
    (net (code "37") (name "IO5") (class "Default")
      (node (ref "J15") (pin "6") (pinfunction "6_6") (pintype "passive"))
      (node (ref "U4") (pin "5") (pinfunction "(OC3A/AIN1)PE3_5") (pintype "bidirectional"))
    )
    (net (code "38") (name "IO6") (class "Default")
      (node (ref "J15") (pin "7") (pinfunction "7_7") (pintype "passive"))
      (node (ref "U4") (pin "15") (pinfunction "PH3(OC4A)_15") (pintype "bidirectional"))
    )
    (net (code "39") (name "IO7") (class "Default")
      (node (ref "J15") (pin "8") (pinfunction "8_8") (pintype "passive"))
      (node (ref "U4") (pin "16") (pinfunction "PH4(OC4B)_16") (pintype "bidirectional"))
    )
    (net (code "40") (name "IO8") (class "Default")
      (node (ref "J15") (pin "9") (pinfunction "9_9") (pintype "passive"))
      (node (ref "U4") (pin "17") (pinfunction "PH5(OC4C)_17") (pintype "bidirectional"))
    )
    (net (code "41") (name "IO9") (class "Default")
      (node (ref "J15") (pin "10") (pinfunction "10_10") (pintype "passive"))
      (node (ref "U4") (pin "18") (pinfunction "PH6(OC2B)_18") (pintype "bidirectional"))
    )
    (net (code "42") (name "IO10") (class "Default")
      (node (ref "J15") (pin "11") (pinfunction "11_11") (pintype "passive"))
      (node (ref "U4") (pin "23") (pinfunction "(OC2A/PCINT4)PB4_23") (pintype "bidirectional"))
    )
    (net (code "43") (name "IO11") (class "Default")
      (node (ref "J15") (pin "12") (pinfunction "12_12") (pintype "passive"))
      (node (ref "U4") (pin "24") (pinfunction "(OC1A/PCINT5)PB5_24") (pintype "bidirectional"))
    )
    (net (code "44") (name "IO12") (class "Default")
      (node (ref "J15") (pin "13") (pinfunction "13_13") (pintype "passive"))
      (node (ref "U4") (pin "25") (pinfunction "(OC1B/PCINT6)PB6_25") (pintype "bidirectional"))
    )
    (net (code "45") (name "IO13") (class "Default")
      (node (ref "J15") (pin "14") (pinfunction "14_14") (pintype "passive"))
      (node (ref "R8") (pin "2") (pinfunction "2_2") (pintype "passive"))
      (node (ref "U4") (pin "26") (pinfunction "(OC0A/OC1C/PCINT7)PB7_26") (pintype "bidirectional"))
    )
    (net (code "46") (name "IO14{slash}TX3") (class "Default")
      (node (ref "J4") (pin "8") (pinfunction "8_8") (pintype "passive"))
      (node (ref "U4") (pin "64") (pinfunction "PJ1(TXD3/PCINT10)_64") (pintype "bidirectional"))
    )
    (net (code "47") (name "IO15{slash}RX3") (class "Default")
      (node (ref "J4") (pin "7") (pinfunction "7_7") (pintype "passive"))
      (node (ref "U4") (pin "63") (pinfunction "PJ0(RXD3/PCINT9)_63") (pintype "bidirectional"))
    )
    (net (code "48") (name "IO16{slash}TX2") (class "Default")
      (node (ref "J4") (pin "6") (pinfunction "6_6") (pintype "passive"))
      (node (ref "U4") (pin "13") (pinfunction "PH1(TXD2)_13") (pintype "bidirectional"))
    )
    (net (code "49") (name "IO17{slash}RX2") (class "Default")
      (node (ref "J4") (pin "5") (pinfunction "5_5") (pintype "passive"))
      (node (ref "U4") (pin "12") (pinfunction "PH0(RXD2)_12") (pintype "bidirectional"))
    )
    (net (code "50") (name "IO18{slash}TX1") (class "Default")
      (node (ref "J12") (pin "2") (pinfunction "2_2") (pintype "passive"))
      (node (ref "J4") (pin "4") (pinfunction "4_4") (pintype "passive"))
      (node (ref "U4") (pin "46") (pinfunction "(TXD1/INT3)PD3_46") (pintype "bidirectional"))
    )
    (net (code "51") (name "IO19{slash}RX1") (class "Default")
      (node (ref "J11") (pin "2") (pinfunction "2_2") (pintype "passive"))
      (node (ref "J4") (pin "3") (pinfunction "3_3") (pintype "passive"))
      (node (ref "U4") (pin "45") (pinfunction "(RXD1/INT2)PD2_45") (pintype "bidirectional"))
    )
    (net (code "52") (name "IO20{slash}SDA") (class "Default")
      (node (ref "J16") (pin "1") (pinfunction "1_1") (pintype "passive"))
      (node (ref "J4") (pin "2") (pinfunction "2_2") (pintype "passive"))
      (node (ref "J8") (pin "2") (pinfunction "2_2") (pintype "passive"))
      (node (ref "TP8") (pin "TP") (pinfunction "TP_TP") (pintype "input"))
      (node (ref "U4") (pin "44") (pinfunction "(SDA/INT1)PD1_44") (pintype "bidirectional"))
    )
    (net (code "53") (name "IO21{slash}SCL") (class "Default")
      (node (ref "J16") (pin "2") (pinfunction "2_2") (pintype "passive"))
      (node (ref "J4") (pin "1") (pinfunction "1_1") (pintype "passive"))
      (node (ref "J9") (pin "2") (pinfunction "2_2") (pintype "passive"))
      (node (ref "TP9") (pin "TP") (pinfunction "TP_TP") (pintype "input"))
      (node (ref "U4") (pin "43") (pinfunction "(SCL/INT0)PD0_43") (pintype "bidirectional"))
    )
    (net (code "54") (name "IO22") (class "Default")
      (node (ref "J5") (pin "1") (pinfunction "1_1") (pintype "passive"))
      (node (ref "U4") (pin "78") (pinfunction "(AD0)PA0_78") (pintype "bidirectional"))
    )
    (net (code "55") (name "IO23") (class "Default")
      (node (ref "J5") (pin "2") (pinfunction "2_2") (pintype "passive"))
      (node (ref "U4") (pin "77") (pinfunction "(AD1)PA1_77") (pintype "bidirectional"))
    )
    (net (code "56") (name "IO24") (class "Default")
      (node (ref "J5") (pin "3") (pinfunction "3_3") (pintype "passive"))
      (node (ref "U4") (pin "76") (pinfunction "(AD2)PA2_76") (pintype "bidirectional"))
    )
    (net (code "57") (name "IO25") (class "Default")
      (node (ref "J5") (pin "4") (pinfunction "4_4") (pintype "passive"))
      (node (ref "U4") (pin "75") (pinfunction "(AD3)PA3_75") (pintype "bidirectional"))
    )
    (net (code "58") (name "IO26") (class "Default")
      (node (ref "J5") (pin "5") (pinfunction "5_5") (pintype "passive"))
      (node (ref "U4") (pin "74") (pinfunction "(AD4)PA4_74") (pintype "bidirectional"))
    )
    (net (code "59") (name "IO27") (class "Default")
      (node (ref "J5") (pin "6") (pinfunction "6_6") (pintype "passive"))
      (node (ref "U4") (pin "73") (pinfunction "(AD5)PA5_73") (pintype "bidirectional"))
    )
    (net (code "60") (name "IO28") (class "Default")
      (node (ref "J5") (pin "7") (pinfunction "7_7") (pintype "passive"))
      (node (ref "U4") (pin "72") (pinfunction "(AD6)PA6_72") (pintype "bidirectional"))
    )
    (net (code "61") (name "IO29") (class "Default")
      (node (ref "J5") (pin "8") (pinfunction "8_8") (pintype "passive"))
      (node (ref "U4") (pin "71") (pinfunction "(AD7)PA7_71") (pintype "bidirectional"))
    )
    (net (code "62") (name "IO30") (class "Default")
      (node (ref "J5") (pin "9") (pinfunction "9_9") (pintype "passive"))
      (node (ref "U4") (pin "60") (pinfunction "(A15)PC7_60") (pintype "bidirectional"))
    )
    (net (code "63") (name "IO31") (class "Default")
      (node (ref "J5") (pin "10") (pinfunction "10_10") (pintype "passive"))
      (node (ref "U4") (pin "59") (pinfunction "(A14)PC6_59") (pintype "bidirectional"))
    )
    (net (code "64") (name "IO32") (class "Default")
      (node (ref "J5") (pin "11") (pinfunction "11_11") (pintype "passive"))
      (node (ref "U4") (pin "58") (pinfunction "(A13)PC5_58") (pintype "bidirectional"))
    )
    (net (code "65") (name "IO33") (class "Default")
      (node (ref "J5") (pin "12") (pinfunction "12_12") (pintype "passive"))
      (node (ref "U4") (pin "57") (pinfunction "(A12)PC4_57") (pintype "bidirectional"))
    )
    (net (code "66") (name "IO34") (class "Default")
      (node (ref "J5") (pin "13") (pinfunction "13_13") (pintype "passive"))
      (node (ref "U4") (pin "56") (pinfunction "(A11)PC3_56") (pintype "bidirectional"))
    )
    (net (code "67") (name "IO35") (class "Default")
      (node (ref "J5") (pin "14") (pinfunction "14_14") (pintype "passive"))
      (node (ref "U4") (pin "55") (pinfunction "(A10)PC2_55") (pintype "bidirectional"))
    )
    (net (code "68") (name "IO36") (class "Default")
      (node (ref "J5") (pin "15") (pinfunction "15_15") (pintype "passive"))
      (node (ref "U4") (pin "54") (pinfunction "(A9)PC1_54") (pintype "bidirectional"))
    )
    (net (code "69") (name "IO37") (class "Default")
      (node (ref "J5") (pin "16") (pinfunction "16_16") (pintype "passive"))
      (node (ref "U4") (pin "53") (pinfunction "(A8)PC0_53") (pintype "bidirectional"))
    )
    (net (code "70") (name "IO38") (class "Default")
      (node (ref "J7") (pin "1") (pinfunction "1_1") (pintype "passive"))
      (node (ref "U4") (pin "50") (pinfunction "(T0)PD7_50") (pintype "bidirectional"))
    )
    (net (code "71") (name "IO39") (class "Default")
      (node (ref "J7") (pin "2") (pinfunction "2_2") (pintype "passive"))
      (node (ref "U4") (pin "70") (pinfunction "(ALE)PG2_70") (pintype "bidirectional"))
    )
    (net (code "72") (name "IO40") (class "Default")
      (node (ref "J7") (pin "3") (pinfunction "3_3") (pintype "passive"))
      (node (ref "U4") (pin "52") (pinfunction "(RD)PG1_52") (pintype "bidirectional"))
    )
    (net (code "73") (name "IO41") (class "Default")
      (node (ref "J7") (pin "4") (pinfunction "4_4") (pintype "passive"))
      (node (ref "U4") (pin "51") (pinfunction "(WR)PG0_51") (pintype "bidirectional"))
    )
    (net (code "74") (name "IO42") (class "Default")
      (node (ref "J7") (pin "5") (pinfunction "5_5") (pintype "passive"))
      (node (ref "U4") (pin "42") (pinfunction "PL7_42") (pintype "bidirectional"))
    )
    (net (code "75") (name "IO43") (class "Default")
      (node (ref "J7") (pin "6") (pinfunction "6_6") (pintype "passive"))
      (node (ref "U4") (pin "41") (pinfunction "PL6_41") (pintype "bidirectional"))
    )
    (net (code "76") (name "IO44") (class "Default")
      (node (ref "J7") (pin "7") (pinfunction "7_7") (pintype "passive"))
      (node (ref "U4") (pin "40") (pinfunction "PL5(OC5C)_40") (pintype "bidirectional"))
    )
    (net (code "77") (name "IO45") (class "Default")
      (node (ref "J7") (pin "8") (pinfunction "8_8") (pintype "passive"))
      (node (ref "U4") (pin "39") (pinfunction "PL4(OC5B)_39") (pintype "bidirectional"))
    )
    (net (code "78") (name "IO46") (class "Default")
      (node (ref "J13") (pin "1") (pinfunction "1_1") (pintype "passive"))
      (node (ref "J7") (pin "9") (pinfunction "9_9") (pintype "passive"))
      (node (ref "U4") (pin "38") (pinfunction "PL3(OC5A)_38") (pintype "bidirectional"))
    )
    (net (code "79") (name "IO47") (class "Default")
      (node (ref "J7") (pin "10") (pinfunction "10_10") (pintype "passive"))
      (node (ref "OLED") (pin "CS") (pinfunction "CS_CS") (pintype "bidirectional"))
      (node (ref "U4") (pin "37") (pinfunction "PL2(T5)_37") (pintype "bidirectional"))
    )
    (net (code "80") (name "IO48") (class "Default")
      (node (ref "J7") (pin "11") (pinfunction "11_11") (pintype "passive"))
      (node (ref "OLED") (pin "DC") (pinfunction "DC_DC") (pintype "bidirectional"))
      (node (ref "U4") (pin "36") (pinfunction "PL1(ICP5)_36") (pintype "bidirectional"))
    )
    (net (code "81") (name "IO49") (class "Default")
      (node (ref "J7") (pin "12") (pinfunction "12_12") (pintype "passive"))
      (node (ref "OLED") (pin "RES") (pinfunction "RES_RES") (pintype "bidirectional"))
      (node (ref "U4") (pin "35") (pinfunction "PL0(ICP4)_35") (pintype "bidirectional"))
    )
    (net (code "82") (name "IO50{slash}MISO") (class "Default")
      (node (ref "J2") (pin "1") (pinfunction "1_1") (pintype "passive"))
      (node (ref "J7") (pin "13") (pinfunction "13_13") (pintype "passive"))
      (node (ref "U4") (pin "22") (pinfunction "(MISO/PCINT3)PB3_22") (pintype "bidirectional"))
    )
    (net (code "83") (name "IO51{slash}MOSI") (class "Default")
      (node (ref "J2") (pin "4") (pinfunction "4_4") (pintype "passive"))
      (node (ref "J7") (pin "14") (pinfunction "14_14") (pintype "passive"))
      (node (ref "OLED") (pin "D1/MOSI") (pinfunction "D1/MOSI_D1/MOSI") (pintype "bidirectional"))
      (node (ref "U4") (pin "21") (pinfunction "(MOSI/PCINT2)PB2_21") (pintype "bidirectional"))
    )
    (net (code "84") (name "IO52{slash}SCK") (class "Default")
      (node (ref "J2") (pin "3") (pinfunction "3_3") (pintype "passive"))
      (node (ref "J7") (pin "15") (pinfunction "15_15") (pintype "passive"))
      (node (ref "OLED") (pin "D0/CLK") (pinfunction "D0/CLK_D0/CLK") (pintype "bidirectional"))
      (node (ref "U4") (pin "20") (pinfunction "(SCK/PCINT1)PB1_20") (pintype "bidirectional"))
    )
    (net (code "85") (name "IO53{slash}SS") (class "Default")
      (node (ref "J7") (pin "16") (pinfunction "16_16") (pintype "passive"))
      (node (ref "U4") (pin "19") (pinfunction "(SS/PCINT0)PB0_19") (pintype "bidirectional"))
    )
    (net (code "86") (name "LED_DO") (class "Default")
      (node (ref "J14") (pin "9") (pinfunction "9_9") (pintype "passive"))
      (node (ref "RGB_LED") (pin "2") (pinfunction "DO_2") (pintype "bidirectional"))
    )
    (net (code "87") (name "Net-(C10-Pad1)") (class "Default")
      (node (ref "C10") (pin "1") (pinfunction "1_1") (pintype "passive"))
      (node (ref "J1") (pin "VBUS") (pinfunction "VBUS_VBUS") (pintype "power_in"))
      (node (ref "PTC") (pin "1") (pinfunction "1_1") (pintype "bidirectional"))
    )
    (net (code "88") (name "Net-(D1-PadA)") (class "Default")
      (node (ref "D1") (pin "A") (pinfunction "A_A") (pintype "passive"))
      (node (ref "R12") (pin "1") (pinfunction "1_1") (pintype "passive"))
    )
    (net (code "89") (name "Net-(D2-PadA)") (class "Default")
      (node (ref "D2") (pin "A") (pinfunction "A_A") (pintype "passive"))
      (node (ref "R16") (pin "1") (pinfunction "1_1") (pintype "passive"))
    )
    (net (code "90") (name "Net-(D3-PadA)") (class "Default")
      (node (ref "D3") (pin "A") (pinfunction "A_A") (pintype "passive"))
      (node (ref "R8") (pin "1") (pinfunction "1_1") (pintype "passive"))
    )
    (net (code "91") (name "Net-(D4-PadA)") (class "Default")
      (node (ref "D4") (pin "A") (pinfunction "A_A") (pintype "passive"))
      (node (ref "J3") (pin "PWR") (pinfunction "PWR_PWR") (pintype "bidirectional"))
    )
    (net (code "92") (name "Net-(D5-PadA)") (class "Default")
      (node (ref "D5") (pin "A") (pinfunction "A_A") (pintype "passive"))
      (node (ref "R2") (pin "1") (pinfunction "1_1") (pintype "passive"))
    )
    (net (code "93") (name "Net-(J3-GND)") (class "Default")
      (node (ref "J3") (pin "GND@2") (pinfunction "GND_GND@2") (pintype "bidirectional"))
      (node (ref "Q1") (pin "1") (pinfunction "G_1") (pintype "bidirectional"))
      (node (ref "R4") (pin "1") (pinfunction "1_1") (pintype "passive"))
    )
    (net (code "94") (name "Net-(J13-Pad2)") (class "Default")
      (node (ref "J13") (pin "2") (pinfunction "2_2") (pintype "passive"))
      (node (ref "R20") (pin "1") (pinfunction "1_1") (pintype "passive"))
    )
    (net (code "95") (name "Net-(Q2-D)") (class "Default")
      (node (ref "J8") (pin "1") (pinfunction "1_1") (pintype "passive"))
      (node (ref "Q2") (pin "3") (pinfunction "D_3") (pintype "passive"))
      (node (ref "R11") (pin "1") (pinfunction "1_1") (pintype "passive"))
    )
    (net (code "96") (name "Net-(Q3-D)") (class "Default")
      (node (ref "J9") (pin "1") (pinfunction "1_1") (pintype "passive"))
      (node (ref "Q3") (pin "3") (pinfunction "D_3") (pintype "passive"))
      (node (ref "R14") (pin "1") (pinfunction "1_1") (pintype "passive"))
    )
    (net (code "97") (name "Net-(Q4-D)") (class "Default")
      (node (ref "J11") (pin "1") (pinfunction "1_1") (pintype "passive"))
      (node (ref "Q4") (pin "3") (pinfunction "D_3") (pintype "passive"))
      (node (ref "R17") (pin "1") (pinfunction "1_1") (pintype "passive"))
    )
    (net (code "98") (name "Net-(Q5-D)") (class "Default")
      (node (ref "J12") (pin "1") (pinfunction "1_1") (pintype "passive"))
      (node (ref "Q5") (pin "3") (pinfunction "D_3") (pintype "passive"))
      (node (ref "R19") (pin "1") (pinfunction "1_1") (pintype "passive"))
    )
    (net (code "99") (name "Net-(RGB_LED-DI)") (class "Default")
      (node (ref "R20") (pin "2") (pinfunction "2_2") (pintype "passive"))
      (node (ref "RGB_LED") (pin "4") (pinfunction "DI_4") (pintype "bidirectional"))
    )
    (net (code "100") (name "Net-(U1-LDR)") (class "Default")
      (node (ref "U1") (pin "3") (pinfunction "LDR_3") (pintype "bidirectional"))
      (node (ref "U1") (pin "4") (pinfunction "LEDK_4") (pintype "bidirectional"))
    )
    (net (code "101") (name "Net-(U2-UD+)") (class "Default")
      (node (ref "J1") (pin "D+") (pinfunction "D+_D+") (pintype "bidirectional"))
      (node (ref "U2") (pin "5") (pinfunction "UD+_5") (pintype "bidirectional"))
    )
    (net (code "102") (name "Net-(U2-UD-)") (class "Default")
      (node (ref "J1") (pin "D-") (pinfunction "D-_D-") (pintype "bidirectional"))
      (node (ref "U2") (pin "6") (pinfunction "UD-_6") (pintype "bidirectional"))
    )
    (net (code "103") (name "Net-(U2-V3)") (class "Default")
      (node (ref "C17") (pin "1") (pinfunction "1_1") (pintype "passive"))
      (node (ref "U2") (pin "4") (pinfunction "V3_4") (pintype "bidirectional"))
    )
    (net (code "104") (name "Net-(U4-XTAL1)") (class "Default")
      (node (ref "C9") (pin "2") (pinfunction "2_2") (pintype "passive"))
      (node (ref "U4") (pin "34") (pinfunction "XTAL1_34") (pintype "input"))
      (node (ref "Y2") (pin "1") (pinfunction "1_1") (pintype "passive"))
    )
    (net (code "105") (name "Net-(U4-XTAL2)") (class "Default")
      (node (ref "C7") (pin "2") (pinfunction "2_2") (pintype "passive"))
      (node (ref "U4") (pin "33") (pinfunction "XTAL2_33") (pintype "output"))
      (node (ref "Y2") (pin "2") (pinfunction "2_2") (pintype "passive"))
    )
    (net (code "106") (name "Net-(U6-SDO)") (class "Default")
      (node (ref "JP1") (pin "2") (pinfunction "2_2") (pintype "passive"))
      (node (ref "R7") (pin "1") (pinfunction "1_1") (pintype "passive"))
      (node (ref "U6") (pin "5") (pinfunction "SDO_5") (pintype "bidirectional"))
    )
    (net (code "107") (name "Net-(U7-SA0{slash}SDO)") (class "Default")
      (node (ref "JP2") (pin "2") (pinfunction "2_2") (pintype "passive"))
      (node (ref "R9") (pin "1") (pinfunction "1_1") (pintype "passive"))
      (node (ref "U7") (pin "7") (pinfunction "SA0/SDO_7") (pintype "bidirectional"))
    )
    (net (code "108") (name "Net-(U7-~{CS}{slash}MODE)") (class "Default")
      (node (ref "R21") (pin "1") (pinfunction "1_1") (pintype "passive"))
      (node (ref "U7") (pin "8") (pinfunction "~{CS}/MODE_8") (pintype "bidirectional"))
    )
    (net (code "109") (name "PROX_INT") (class "Default")
      (node (ref "J14") (pin "7") (pinfunction "7_7") (pintype "passive"))
      (node (ref "R1") (pin "1") (pinfunction "1_1") (pintype "passive"))
      (node (ref "U1") (pin "2") (pinfunction "INT_2") (pintype "bidirectional"))
    )
    (net (code "110") (name "RESET") (class "Default")
      (node (ref "C13") (pin "2") (pinfunction "2_2") (pintype "passive"))
      (node (ref "J10") (pin "2") (pinfunction "2_2") (pintype "passive"))
      (node (ref "J2") (pin "5") (pinfunction "5_5") (pintype "passive"))
      (node (ref "R3") (pin "1") (pinfunction "1_1") (pintype "passive"))
      (node (ref "RESET") (pin "3") (pinfunction "2_3") (pintype "passive"))
      (node (ref "U4") (pin "30") (pinfunction "RESET_30") (pintype "input"))
    )
    (net (code "111") (name "SCL_SEN") (class "Default")
      (node (ref "Q3") (pin "2") (pinfunction "S_2") (pintype "passive"))
      (node (ref "R13") (pin "1") (pinfunction "1_1") (pintype "passive"))
      (node (ref "TP12") (pin "TP") (pinfunction "TP_TP") (pintype "input"))
      (node (ref "U1") (pin "7") (pinfunction "SCL_7") (pintype "bidirectional"))
      (node (ref "U6") (pin "4") (pinfunction "SCK_4") (pintype "input"))
      (node (ref "U7") (pin "4") (pinfunction "SCL/SPC_4") (pintype "bidirectional"))
    )
    (net (code "112") (name "SDA_SEN") (class "Default")
      (node (ref "Q2") (pin "2") (pinfunction "S_2") (pintype "passive"))
      (node (ref "R10") (pin "1") (pinfunction "1_1") (pintype "passive"))
      (node (ref "TP11") (pin "TP") (pinfunction "TP_TP") (pintype "input"))
      (node (ref "U1") (pin "1") (pinfunction "SDA_1") (pintype "bidirectional"))
      (node (ref "U6") (pin "3") (pinfunction "SDI_3") (pintype "bidirectional"))
      (node (ref "U7") (pin "6") (pinfunction "SDA/SDI_6") (pintype "bidirectional"))
    )
    (net (code "113") (name "SHLD") (class "Default")
      (node (ref "J1") (pin "SHIELD") (pinfunction "SHIELD_SHIELD") (pintype "bidirectional"))
      (node (ref "J1") (pin "SHIELD10") (pinfunction "SHIELD_SHIELD10") (pintype "bidirectional"))
      (node (ref "J1") (pin "SHIELD2") (pinfunction "SHIELD_SHIELD2") (pintype "bidirectional"))
      (node (ref "J1") (pin "SHIELD3") (pinfunction "SHIELD_SHIELD3") (pintype "bidirectional"))
      (node (ref "J1") (pin "SHIELD4") (pinfunction "SHIELD_SHIELD4") (pintype "bidirectional"))
      (node (ref "J1") (pin "SHIELD5") (pinfunction "SHIELD_SHIELD5") (pintype "bidirectional"))
      (node (ref "J1") (pin "SHIELD6") (pinfunction "SHIELD_SHIELD6") (pintype "bidirectional"))
      (node (ref "J1") (pin "SHIELD7") (pinfunction "SHIELD_SHIELD7") (pintype "bidirectional"))
      (node (ref "J1") (pin "SHIELD8") (pinfunction "SHIELD_SHIELD8") (pintype "bidirectional"))
      (node (ref "J1") (pin "SHIELD9") (pinfunction "SHIELD_SHIELD9") (pintype "bidirectional"))
    )
    (net (code "114") (name "USBVCC") (class "Default")
      (node (ref "C12") (pin "1") (pinfunction "1_1") (pintype "passive"))
      (node (ref "C15") (pin "+") (pinfunction "+_+") (pintype "passive"))
      (node (ref "PTC") (pin "2") (pinfunction "2_2") (pintype "bidirectional"))
      (node (ref "Q1") (pin "3") (pinfunction "D_3") (pintype "bidirectional"))
    )
    (net (code "115") (name "VIN") (class "Default")
      (node (ref "C5") (pin "+") (pinfunction "+_+") (pintype "passive"))
      (node (ref "D4") (pin "C") (pinfunction "C_C") (pintype "passive"))
      (node (ref "J10") (pin "8") (pinfunction "8_8") (pintype "passive"))
      (node (ref "TP7") (pin "TP") (pinfunction "TP_TP") (pintype "input"))
      (node (ref "U8") (pin "3") (pinfunction "VIN_3") (pintype "input"))
    )
    (net (code "116") (name "unconnected-(J1-PadID)") (class "Default")
      (node (ref "J1") (pin "ID") (pinfunction "ID_ID") (pintype "bidirectional"))
    )
    (net (code "117") (name "unconnected-(U2-R232-Pad15)") (class "Default")
      (node (ref "U2") (pin "15") (pinfunction "R232_15") (pintype "bidirectional"))
    )
    (net (code "118") (name "unconnected-(U2-~{CTS}-Pad9)") (class "Default")
      (node (ref "U2") (pin "9") (pinfunction "~{CTS}_9") (pintype "bidirectional"))
    )
    (net (code "119") (name "unconnected-(U2-~{DCD}-Pad12)") (class "Default")
      (node (ref "U2") (pin "12") (pinfunction "~{DCD}_12") (pintype "bidirectional"))
    )
    (net (code "120") (name "unconnected-(U2-~{DSR}-Pad10)") (class "Default")
      (node (ref "U2") (pin "10") (pinfunction "~{DSR}_10") (pintype "bidirectional"))
    )
    (net (code "121") (name "unconnected-(U2-~{RI}-Pad11)") (class "Default")
      (node (ref "U2") (pin "11") (pinfunction "~{RI}_11") (pintype "bidirectional"))
    )
    (net (code "122") (name "unconnected-(U2-~{RTS}-Pad14)") (class "Default")
      (node (ref "U2") (pin "14") (pinfunction "~{RTS}_14") (pintype "bidirectional"))
    )
    (net (code "123") (name "unconnected-(U4-(CLKO{slash}ICP3{slash}INT7)PE7-Pad9)") (class "Default")
      (node (ref "U4") (pin "9") (pinfunction "(CLKO/ICP3/INT7)PE7_9") (pintype "bidirectional"))
    )
    (net (code "124") (name "unconnected-(U4-(ICP1)PD4-Pad47)") (class "Default")
      (node (ref "U4") (pin "47") (pinfunction "(ICP1)PD4_47") (pintype "bidirectional"))
    )
    (net (code "125") (name "unconnected-(U4-(T1)PD6-Pad49)") (class "Default")
      (node (ref "U4") (pin "49") (pinfunction "(T1)PD6_49") (pintype "bidirectional"))
    )
    (net (code "126") (name "unconnected-(U4-(T3{slash}INT6)PE6-Pad8)") (class "Default")
      (node (ref "U4") (pin "8") (pinfunction "(T3/INT6)PE6_8") (pintype "bidirectional"))
    )
    (net (code "127") (name "unconnected-(U4-(TOSC1)PG4-Pad29)") (class "Default")
      (node (ref "U4") (pin "29") (pinfunction "(TOSC1)PG4_29") (pintype "bidirectional"))
    )
    (net (code "128") (name "unconnected-(U4-(TOSC2)PG3-Pad28)") (class "Default")
      (node (ref "U4") (pin "28") (pinfunction "(TOSC2)PG3_28") (pintype "bidirectional"))
    )
    (net (code "129") (name "unconnected-(U4-(XCK0{slash}AIN0)PE2-Pad4)") (class "Default")
      (node (ref "U4") (pin "4") (pinfunction "(XCK0/AIN0)PE2_4") (pintype "bidirectional"))
    )
    (net (code "130") (name "unconnected-(U4-(XCK1)PD5-Pad48)") (class "Default")
      (node (ref "U4") (pin "48") (pinfunction "(XCK1)PD5_48") (pintype "bidirectional"))
    )
    (net (code "131") (name "unconnected-(U4-PH2(XCK2)-Pad14)") (class "Default")
      (node (ref "U4") (pin "14") (pinfunction "PH2(XCK2)_14") (pintype "bidirectional"))
    )
    (net (code "132") (name "unconnected-(U4-PH7(T4)-Pad27)") (class "Default")
      (node (ref "U4") (pin "27") (pinfunction "PH7(T4)_27") (pintype "bidirectional"))
    )
    (net (code "133") (name "unconnected-(U4-PJ2(XCK3{slash}PCINT11)-Pad65)") (class "Default")
      (node (ref "U4") (pin "65") (pinfunction "PJ2(XCK3/PCINT11)_65") (pintype "bidirectional"))
    )
    (net (code "134") (name "unconnected-(U4-PJ3(PCINT12)-Pad66)") (class "Default")
      (node (ref "U4") (pin "66") (pinfunction "PJ3(PCINT12)_66") (pintype "bidirectional"))
    )
    (net (code "135") (name "unconnected-(U4-PJ4(PCINT13)-Pad67)") (class "Default")
      (node (ref "U4") (pin "67") (pinfunction "PJ4(PCINT13)_67") (pintype "bidirectional"))
    )
    (net (code "136") (name "unconnected-(U4-PJ5(PCINT14)-Pad68)") (class "Default")
      (node (ref "U4") (pin "68") (pinfunction "PJ5(PCINT14)_68") (pintype "bidirectional"))
    )
    (net (code "137") (name "unconnected-(U4-PJ6(PCINT15)-Pad69)") (class "Default")
      (node (ref "U4") (pin "69") (pinfunction "PJ6(PCINT15)_69") (pintype "bidirectional"))
    )
    (net (code "138") (name "unconnected-(U4-PJ7-Pad79)") (class "Default")
      (node (ref "U4") (pin "79") (pinfunction "PJ7_79") (pintype "bidirectional"))
    )
  )
)
